# debug_LED.net
KiCad netlist of a schematic drawn in Altium Designer
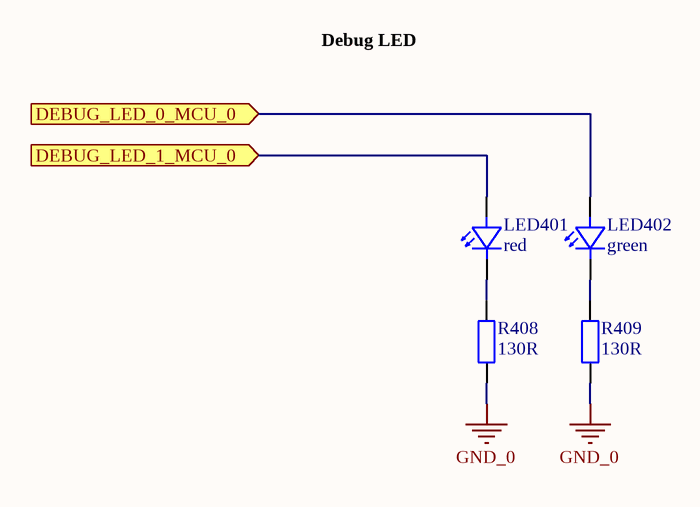
[diagram p0: debug_LED.SchDoc]

(export (version "E")
  (design (tool "Eeschema 10.0.6"))
  (components
    (comp (ref "LED401")
      (value "red")
      (footprint "LEDC1608X07N")
      (description "LED")
      (fields (field (name "PART NUMBER") "gen_LED_0603_red"))
      (libsource (lib "OE750") (part "D_LED"))
    )
    (comp (ref "LED402")
      (value "green")
      (footprint "LEDC1608X07N")
      (description "LED")
      (fields (field (name "PART NUMBER") "gen_LED_0603_green"))
      (libsource (lib "OE750") (part "D_LED"))
    )
    (comp (ref "R408")
      (value "130R")
      (footprint "RESC1608X05N")
      (description "SMD Resistor 130R 0603")
      (fields (field (name "PART NUMBER") "gen_R_130R_0603") (field (name "TOLERANCE") "1%"))
      (libsource (lib "OE750") (part "R"))
    )
    (comp (ref "R409")
      (value "130R")
      (footprint "RESC1608X05N")
      (description "SMD Resistor 130R 0603")
      (fields (field (name "PART NUMBER") "gen_R_130R_0603") (field (name "TOLERANCE") "1%"))
      (libsource (lib "OE750") (part "R"))
    )
  )
  (nets
    (net (code "1") (name "/DEBUG_LED_0_MCU_0") (class "Default")
      (node (ref "LED402") (pin "2") (pinfunction "A_2") (pintype "passive"))
    )
    (net (code "2") (name "/DEBUG_LED_1_MCU_0") (class "Default")
      (node (ref "LED401") (pin "2") (pinfunction "A_2") (pintype "passive"))
    )
    (net (code "3") (name "GND_0") (class "Default")
      (node (ref "R408") (pin "1") (pinfunction "1_1") (pintype "passive"))
      (node (ref "R409") (pin "1") (pinfunction "1_1") (pintype "passive"))
    )
    (net (code "4") (name "Net-(LED401-C)") (class "Default")
      (node (ref "LED401") (pin "1") (pinfunction "C_1") (pintype "passive"))
      (node (ref "R408") (pin "2") (pinfunction "2_2") (pintype "passive"))
    )
    (net (code "5") (name "Net-(LED402-C)") (class "Default")
      (node (ref "LED402") (pin "1") (pinfunction "C_1") (pintype "passive"))
      (node (ref "R409") (pin "2") (pinfunction "2_2") (pintype "passive"))
    )
  )
)
